# Enclosure_Front.net
KiCad netlist of a schematic drawn in EAGLE
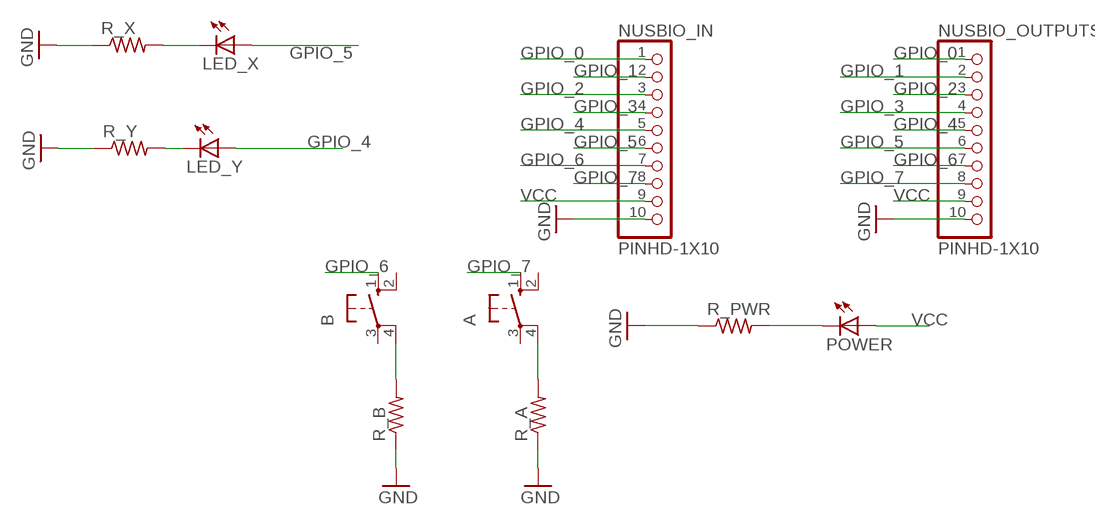
[diagram p0: schematic, sheet 1]

(export (version "E")
  (design (tool "Eeschema 10.0.6"))
  (components
    (comp (ref "A")
      (value "10-XX")
      (footprint "eagle-import:B3F-10XX")
      (fields (field (name "MPN") "B3F-1000"))
      (libsource (lib "eagle-import") (part "10-XX"))
    )
    (comp (ref "B")
      (value "10-XX")
      (footprint "eagle-import:B3F-10XX")
      (fields (field (name "MPN") "B3F-1000"))
      (libsource (lib "eagle-import") (part "10-XX"))
    )
    (comp (ref "LED_X")
      (value "LEDSMT1206")
      (footprint "eagle-import:1206")
      (libsource (lib "eagle-import") (part "LEDSMT1206"))
    )
    (comp (ref "LED_Y")
      (value "LEDSMT1206")
      (footprint "eagle-import:1206")
      (libsource (lib "eagle-import") (part "LEDSMT1206"))
    )
    (comp (ref "NUSBIO_IN")
      (value "PINHD-1X10")
      (footprint "eagle-import:1X10-BIG")
      (libsource (lib "eagle-import") (part "PINHD-1X10"))
    )
    (comp (ref "NUSBIO_OUTPUTS")
      (value "PINHD-1X10")
      (footprint "eagle-import:1X10-BIG")
      (libsource (lib "eagle-import") (part "PINHD-1X10"))
    )
    (comp (ref "POWER")
      (value "LEDSMT1206")
      (footprint "eagle-import:1206")
      (libsource (lib "eagle-import") (part "LEDSMT1206"))
    )
    (comp (ref "R_A")
      (value "R-US_R1206")
      (footprint "eagle-import:R1206")
      (libsource (lib "eagle-import") (part "R-US_R1206"))
    )
    (comp (ref "R_B")
      (value "R-US_R1206")
      (footprint "eagle-import:R1206")
      (libsource (lib "eagle-import") (part "R-US_R1206"))
    )
    (comp (ref "R_PWR")
      (value "R-US_R1206")
      (footprint "eagle-import:R1206")
      (libsource (lib "eagle-import") (part "R-US_R1206"))
    )
    (comp (ref "R_X")
      (value "R-US_R1206")
      (footprint "eagle-import:R1206")
      (libsource (lib "eagle-import") (part "R-US_R1206"))
    )
    (comp (ref "R_Y")
      (value "R-US_R1206")
      (footprint "eagle-import:R1206")
      (libsource (lib "eagle-import") (part "R-US_R1206"))
    )
  )
  (nets
    (net (code "1") (name "/GPIO_0") (class "Default")
      (node (ref "NUSBIO_IN") (pin "1") (pinfunction "1_1") (pintype "passive"))
      (node (ref "NUSBIO_OUTPUTS") (pin "1") (pinfunction "1_1") (pintype "passive"))
    )
    (net (code "2") (name "/GPIO_1") (class "Default")
      (node (ref "NUSBIO_IN") (pin "2") (pinfunction "2_2") (pintype "passive"))
      (node (ref "NUSBIO_OUTPUTS") (pin "2") (pinfunction "2_2") (pintype "passive"))
    )
    (net (code "3") (name "/GPIO_2") (class "Default")
      (node (ref "NUSBIO_IN") (pin "3") (pinfunction "3_3") (pintype "passive"))
      (node (ref "NUSBIO_OUTPUTS") (pin "3") (pinfunction "3_3") (pintype "passive"))
    )
    (net (code "4") (name "/GPIO_3") (class "Default")
      (node (ref "NUSBIO_IN") (pin "4") (pinfunction "4_4") (pintype "passive"))
      (node (ref "NUSBIO_OUTPUTS") (pin "4") (pinfunction "4_4") (pintype "passive"))
    )
    (net (code "5") (name "/GPIO_4") (class "Default")
      (node (ref "LED_Y") (pin "A") (pinfunction "A_A") (pintype "passive"))
      (node (ref "NUSBIO_IN") (pin "5") (pinfunction "5_5") (pintype "passive"))
      (node (ref "NUSBIO_OUTPUTS") (pin "5") (pinfunction "5_5") (pintype "passive"))
    )
    (net (code "6") (name "/GPIO_5") (class "Default")
      (node (ref "LED_X") (pin "A") (pinfunction "A_A") (pintype "passive"))
      (node (ref "NUSBIO_IN") (pin "6") (pinfunction "6_6") (pintype "passive"))
      (node (ref "NUSBIO_OUTPUTS") (pin "6") (pinfunction "6_6") (pintype "passive"))
    )
    (net (code "7") (name "/GPIO_6") (class "Default")
      (node (ref "B") (pin "1") (pinfunction "S_1") (pintype "passive"))
      (node (ref "NUSBIO_IN") (pin "7") (pinfunction "7_7") (pintype "passive"))
      (node (ref "NUSBIO_OUTPUTS") (pin "7") (pinfunction "7_7") (pintype "passive"))
    )
    (net (code "8") (name "/GPIO_7") (class "Default")
      (node (ref "A") (pin "1") (pinfunction "S_1") (pintype "passive"))
      (node (ref "NUSBIO_IN") (pin "8") (pinfunction "8_8") (pintype "passive"))
      (node (ref "NUSBIO_OUTPUTS") (pin "8") (pinfunction "8_8") (pintype "passive"))
    )
    (net (code "9") (name "/VCC") (class "Default")
      (node (ref "NUSBIO_IN") (pin "9") (pinfunction "9_9") (pintype "passive"))
      (node (ref "NUSBIO_OUTPUTS") (pin "9") (pinfunction "9_9") (pintype "passive"))
      (node (ref "POWER") (pin "A") (pinfunction "A_A") (pintype "passive"))
    )
    (net (code "10") (name "GND") (class "Default")
      (node (ref "NUSBIO_IN") (pin "10") (pinfunction "10_10") (pintype "passive"))
      (node (ref "NUSBIO_OUTPUTS") (pin "10") (pinfunction "10_10") (pintype "passive"))
      (node (ref "R_A") (pin "1") (pinfunction "1_1") (pintype "passive"))
      (node (ref "R_B") (pin "1") (pinfunction "1_1") (pintype "passive"))
      (node (ref "R_PWR") (pin "1") (pinfunction "1_1") (pintype "passive"))
      (node (ref "R_X") (pin "1") (pinfunction "1_1") (pintype "passive"))
      (node (ref "R_Y") (pin "1") (pinfunction "1_1") (pintype "passive"))
    )
    (net (code "11") (name "Net-(A-P1)") (class "Default")
      (node (ref "A") (pin "4") (pinfunction "P1_4") (pintype "passive"))
      (node (ref "R_A") (pin "2") (pinfunction "2_2") (pintype "passive"))
    )
    (net (code "12") (name "Net-(B-P1)") (class "Default")
      (node (ref "B") (pin "4") (pinfunction "P1_4") (pintype "passive"))
      (node (ref "R_B") (pin "2") (pinfunction "2_2") (pintype "passive"))
    )
    (net (code "13") (name "Net-(LED_X-PadC)") (class "Default")
      (node (ref "LED_X") (pin "C") (pinfunction "C_C") (pintype "passive"))
      (node (ref "R_X") (pin "2") (pinfunction "2_2") (pintype "passive"))
    )
    (net (code "14") (name "Net-(LED_Y-PadC)") (class "Default")
      (node (ref "LED_Y") (pin "C") (pinfunction "C_C") (pintype "passive"))
      (node (ref "R_Y") (pin "2") (pinfunction "2_2") (pintype "passive"))
    )
    (net (code "15") (name "Net-(POWER-PadC)") (class "Default")
      (node (ref "POWER") (pin "C") (pinfunction "C_C") (pintype "passive"))
      (node (ref "R_PWR") (pin "2") (pinfunction "2_2") (pintype "passive"))
    )
    (net (code "16") (name "unconnected-(A-P-Pad3)") (class "Default")
      (node (ref "A") (pin "3") (pinfunction "P_3") (pintype "passive"))
    )
    (net (code "17") (name "unconnected-(A-S1-Pad2)") (class "Default")
      (node (ref "A") (pin "2") (pinfunction "S1_2") (pintype "passive"))
    )
    (net (code "18") (name "unconnected-(B-P-Pad3)") (class "Default")
      (node (ref "B") (pin "3") (pinfunction "P_3") (pintype "passive"))
    )
    (net (code "19") (name "unconnected-(B-S1-Pad2)") (class "Default")
      (node (ref "B") (pin "2") (pinfunction "S1_2") (pintype "passive"))
    )
  )
)
